# SensadoCalibradoMaquinas_v2.net
KiCad netlist of a schematic drawn in EAGLE
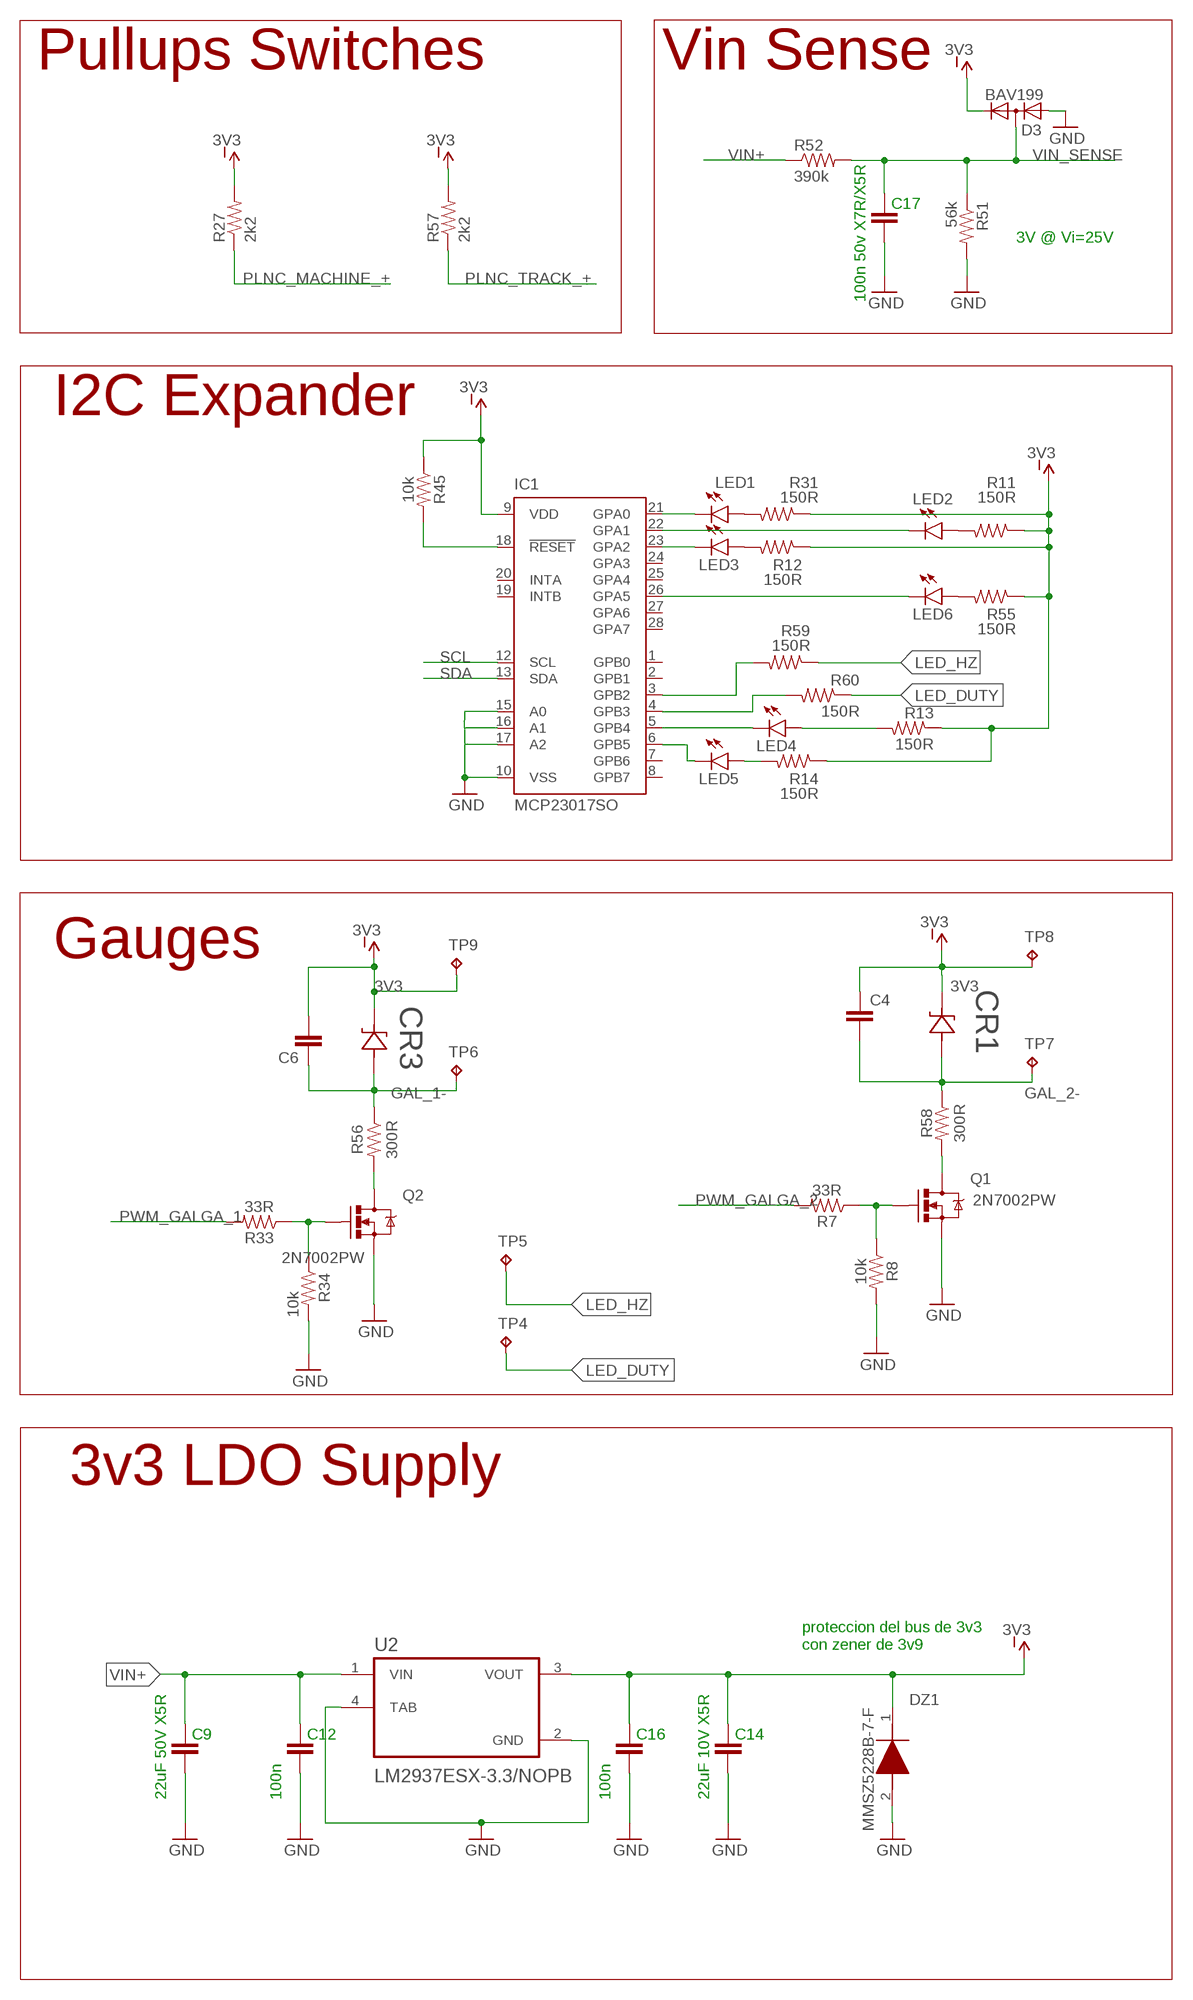
[diagram p0: schematic, sheet 1, part 1 of 2]
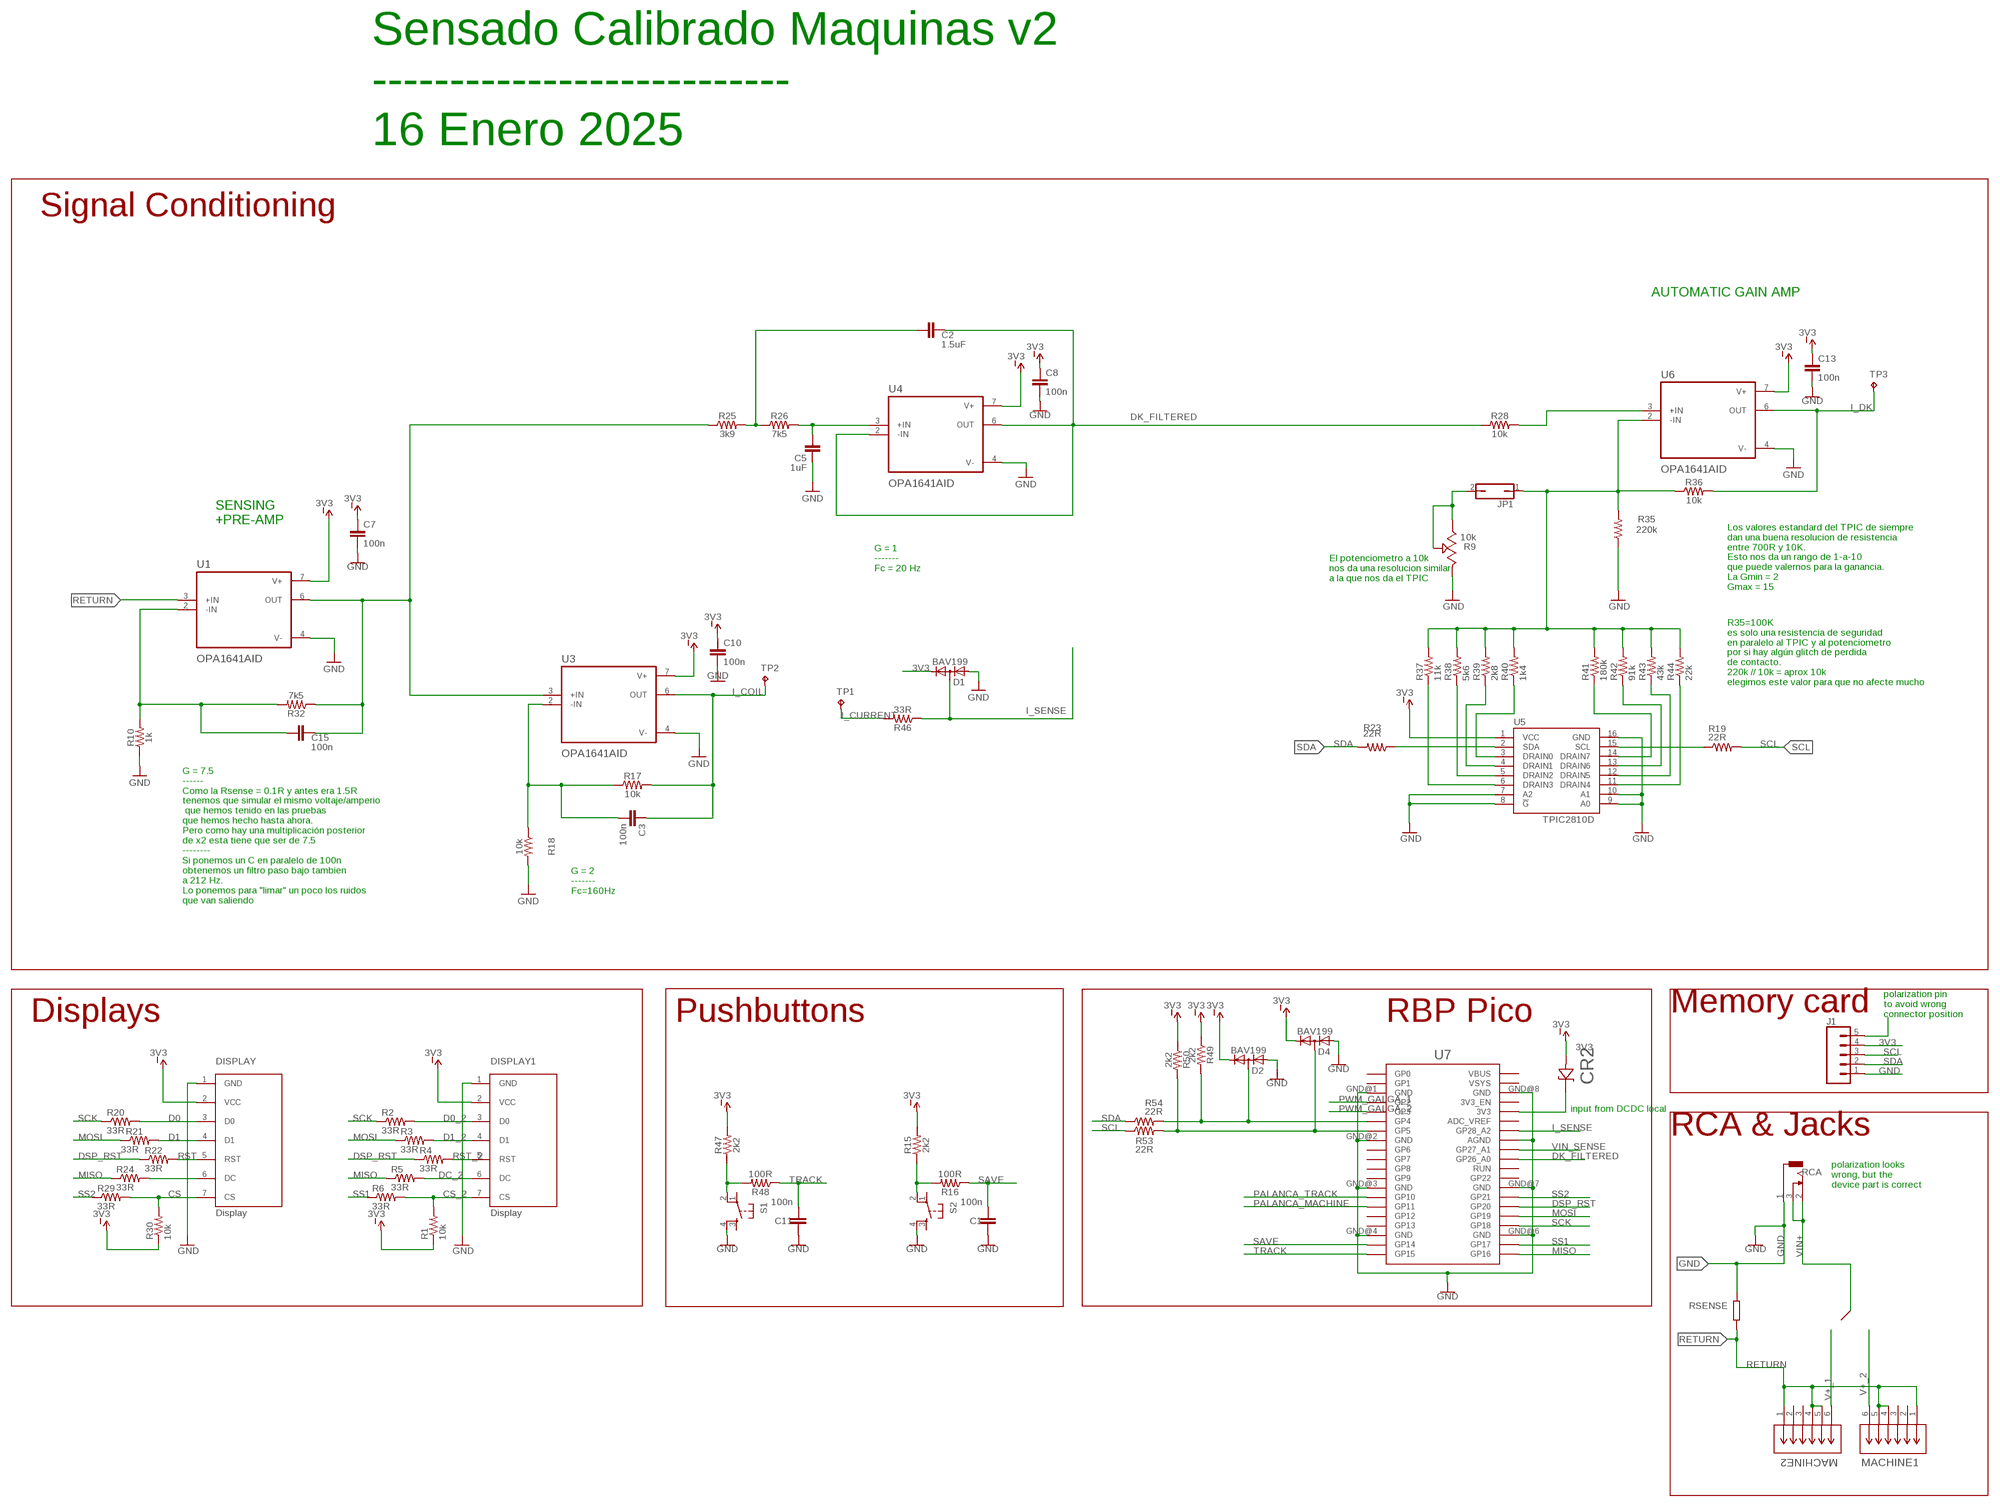
[diagram p1: schematic, sheet 1, part 2 of 2]

(export (version "E")
  (design (tool "Eeschema 10.0.6"))
  (components
    (comp (ref "C1")
      (value "100n")
      (footprint "eagle-import:0805")
      (libsource (lib "eagle-import") (part "1.0UF-0805-25V-(+80/-20%)"))
    )
    (comp (ref "C2")
      (value "1.5uF")
      (footprint "eagle-import:0805")
      (libsource (lib "eagle-import") (part "CAP0805"))
    )
    (comp (ref "C3")
      (value "100n")
      (footprint "eagle-import:0805")
      (libsource (lib "eagle-import") (part "CAP0805"))
    )
    (comp (ref "C4")
      (value "CAP0805")
      (footprint "eagle-import:0805")
      (libsource (lib "eagle-import") (part "CAP0805"))
    )
    (comp (ref "C5")
      (value "1uF")
      (footprint "eagle-import:0805")
      (libsource (lib "eagle-import") (part "CAP0805"))
    )
    (comp (ref "C6")
      (value "CAP0805")
      (footprint "eagle-import:0805")
      (libsource (lib "eagle-import") (part "CAP0805"))
    )
    (comp (ref "C7")
      (value "100n")
      (footprint "eagle-import:0805")
      (libsource (lib "eagle-import") (part "1.0UF-0805-25V-(+80/-20%)"))
    )
    (comp (ref "C8")
      (value "100n")
      (footprint "eagle-import:0805")
      (libsource (lib "eagle-import") (part "1.0UF-0805-25V-(+80/-20%)"))
    )
    (comp (ref "C9")
      (value "22uF 50V X5R")
      (footprint "eagle-import:0805")
      (libsource (lib "eagle-import") (part "CAP0805"))
    )
    (comp (ref "C10")
      (value "100n")
      (footprint "eagle-import:0805")
      (libsource (lib "eagle-import") (part "1.0UF-0805-25V-(+80/-20%)"))
    )
    (comp (ref "C11")
      (value "100n")
      (footprint "eagle-import:0805")
      (libsource (lib "eagle-import") (part "1.0UF-0805-25V-(+80/-20%)"))
    )
    (comp (ref "C12")
      (value "100n")
      (footprint "eagle-import:0805")
      (libsource (lib "eagle-import") (part "CAP0805"))
    )
    (comp (ref "C13")
      (value "100n")
      (footprint "eagle-import:0805")
      (libsource (lib "eagle-import") (part "1.0UF-0805-25V-(+80/-20%)"))
    )
    (comp (ref "C14")
      (value "22uF 10V X5R")
      (footprint "eagle-import:0805")
      (libsource (lib "eagle-import") (part "CAP0805"))
    )
    (comp (ref "C15")
      (value "100n")
      (footprint "eagle-import:0805")
      (libsource (lib "eagle-import") (part "CAP0805"))
    )
    (comp (ref "C16")
      (value "100n")
      (footprint "eagle-import:0805")
      (libsource (lib "eagle-import") (part "CAP0805"))
    )
    (comp (ref "C17")
      (value "100n 50v X7R/X5R")
      (footprint "eagle-import:0805")
      (libsource (lib "eagle-import") (part "CAP0805"))
    )
    (comp (ref "CR1")
      (value "STPS1L40U")
      (footprint "eagle-import:SMB_STM")
      (fields (field (name "COPYRIGHT") "Copyright (C) 2024 Ultra Librarian. All rights reserved."))
      (libsource (lib "eagle-import") (part "STPS1L40U"))
    )
    (comp (ref "CR2")
      (value "STPS1L40U")
      (footprint "eagle-import:SMB_STM")
      (fields (field (name "COPYRIGHT") "Copyright (C) 2024 Ultra Librarian. All rights reserved."))
      (libsource (lib "eagle-import") (part "STPS1L40U"))
    )
    (comp (ref "CR3")
      (value "STPS1L40U")
      (footprint "eagle-import:SMB_STM")
      (fields (field (name "COPYRIGHT") "Copyright (C) 2024 Ultra Librarian. All rights reserved."))
      (libsource (lib "eagle-import") (part "STPS1L40U"))
    )
    (comp (ref "D1")
      (value "BAV199")
      (footprint "eagle-import:SOT23")
      (libsource (lib "eagle-import") (part "BAV199"))
    )
    (comp (ref "D2")
      (value "BAV199")
      (footprint "eagle-import:SOT23")
      (libsource (lib "eagle-import") (part "BAV199"))
    )
    (comp (ref "D3")
      (value "BAV199")
      (footprint "eagle-import:SOT23")
      (libsource (lib "eagle-import") (part "BAV199"))
    )
    (comp (ref "D4")
      (value "BAV199")
      (footprint "eagle-import:SOT23")
      (libsource (lib "eagle-import") (part "BAV199"))
    )
    (comp (ref "DISPLAY")
      (value "Display")
      (footprint "eagle-import:OLED_LCD")
      (libsource (lib "eagle-import") (part "OLED_LCD"))
    )
    (comp (ref "DISPLAY1")
      (value "Display")
      (footprint "eagle-import:OLED_LCD")
      (libsource (lib "eagle-import") (part "OLED_LCD"))
    )
    (comp (ref "DZ1")
      (value "MMSZ5228B-7-F")
      (footprint "eagle-import:SODFL3518X115N")
      (libsource (lib "eagle-import") (part "MMSZ5228B-7-F"))
    )
    (comp (ref "IC1")
      (value "MCP23017SO")
      (footprint "eagle-import:SO28W")
      (libsource (lib "eagle-import") (part "MCP23017SO"))
    )
    (comp (ref "J1")
      (value "CONN_05")
      (footprint "eagle-import:1X05")
      (libsource (lib "eagle-import") (part "CONN_05"))
    )
    (comp (ref "JP1")
      (value "JP1Q")
      (footprint "eagle-import:JP1")
      (libsource (lib "eagle-import") (part "JP1Q"))
    )
    (comp (ref "LED1")
      (value "LED3MM")
      (footprint "eagle-import:LED3MM")
      (libsource (lib "eagle-import") (part "LED3MM"))
    )
    (comp (ref "LED2")
      (value "LED3MM")
      (footprint "eagle-import:LED3MM")
      (libsource (lib "eagle-import") (part "LED3MM"))
    )
    (comp (ref "LED3")
      (value "LED3MM")
      (footprint "eagle-import:LED3MM")
      (libsource (lib "eagle-import") (part "LED3MM"))
    )
    (comp (ref "LED4")
      (value "LED3MM")
      (footprint "eagle-import:LED3MM")
      (libsource (lib "eagle-import") (part "LED3MM"))
    )
    (comp (ref "LED5")
      (value "LED3MM")
      (footprint "eagle-import:LED3MM")
      (libsource (lib "eagle-import") (part "LED3MM"))
    )
    (comp (ref "LED6")
      (value "LED3MM")
      (footprint "eagle-import:LED3MM")
      (libsource (lib "eagle-import") (part "LED3MM"))
    )
    (comp (ref "MACHINE1")
      (value "ACJS-MHDR")
      (footprint "eagle-import:CONN_MHDR_AMP")
      (fields (field (name "COPYRIGHT") "Copyright (C) 2018 Accelerated Designs. All rights reserved"))
      (libsource (lib "eagle-import") (part "ACJS-MHDR"))
    )
    (comp (ref "MACHINE2")
      (value "ACJS-MHDR")
      (footprint "eagle-import:CONN_MHDR_AMP")
      (fields (field (name "COPYRIGHT") "Copyright (C) 2018 Accelerated Designs. All rights reserved"))
      (libsource (lib "eagle-import") (part "ACJS-MHDR"))
    )
    (comp (ref "Q1")
      (value "2N7002PW")
      (footprint "eagle-import:SOT323")
      (libsource (lib "eagle-import") (part "MOSFET-NCHANNEL2N7002PW"))
    )
    (comp (ref "Q2")
      (value "2N7002PW")
      (footprint "eagle-import:SOT323")
      (libsource (lib "eagle-import") (part "MOSFET-NCHANNEL2N7002PW"))
    )
    (comp (ref "R1")
      (value "10k")
      (footprint "eagle-import:0805")
      (libsource (lib "eagle-import") (part "RESISTOR0805"))
    )
    (comp (ref "R2")
      (value "33R")
      (footprint "eagle-import:0805")
      (libsource (lib "eagle-import") (part "RESISTOR0805"))
    )
    (comp (ref "R3")
      (value "33R")
      (footprint "eagle-import:0805")
      (libsource (lib "eagle-import") (part "RESISTOR0805"))
    )
    (comp (ref "R4")
      (value "33R")
      (footprint "eagle-import:0805")
      (libsource (lib "eagle-import") (part "RESISTOR0805"))
    )
    (comp (ref "R5")
      (value "33R")
      (footprint "eagle-import:0805")
      (libsource (lib "eagle-import") (part "RESISTOR0805"))
    )
    (comp (ref "R6")
      (value "33R")
      (footprint "eagle-import:0805")
      (libsource (lib "eagle-import") (part "RESISTOR0805"))
    )
    (comp (ref "R7")
      (value "33R")
      (footprint "eagle-import:0805")
      (libsource (lib "eagle-import") (part "RESISTOR0805"))
    )
    (comp (ref "R8")
      (value "10k")
      (footprint "eagle-import:0805")
      (libsource (lib "eagle-import") (part "RESISTOR0805"))
    )
    (comp (ref "R9")
      (value "10k")
      (footprint "eagle-import:TRIM_PT01-D120D-B104")
      (fields (field (name "MANUFACTURER") "CUI Devices"))
      (libsource (lib "eagle-import") (part "PT01-D120D-B104"))
    )
    (comp (ref "R10")
      (value "1k")
      (footprint "eagle-import:0805")
      (libsource (lib "eagle-import") (part "RESISTOR0805"))
    )
    (comp (ref "R11")
      (value "150R")
      (footprint "eagle-import:0805")
      (libsource (lib "eagle-import") (part "RESISTOR0805"))
    )
    (comp (ref "R12")
      (value "150R")
      (footprint "eagle-import:0805")
      (libsource (lib "eagle-import") (part "RESISTOR0805"))
    )
    (comp (ref "R13")
      (value "150R")
      (footprint "eagle-import:0805")
      (libsource (lib "eagle-import") (part "RESISTOR0805"))
    )
    (comp (ref "R14")
      (value "150R")
      (footprint "eagle-import:0805")
      (libsource (lib "eagle-import") (part "RESISTOR0805"))
    )
    (comp (ref "R15")
      (value "2k2")
      (footprint "eagle-import:0805")
      (libsource (lib "eagle-import") (part "RESISTOR0805"))
    )
    (comp (ref "R16")
      (value "100R")
      (footprint "eagle-import:0805")
      (libsource (lib "eagle-import") (part "RESISTOR0805"))
    )
    (comp (ref "R17")
      (value "10k")
      (footprint "eagle-import:0805")
      (libsource (lib "eagle-import") (part "RESISTOR0805"))
    )
    (comp (ref "R18")
      (value "10k")
      (footprint "eagle-import:0805")
      (libsource (lib "eagle-import") (part "RESISTOR0805"))
    )
    (comp (ref "R19")
      (value "22R")
      (footprint "eagle-import:0805")
      (libsource (lib "eagle-import") (part "RESISTOR0805"))
    )
    (comp (ref "R20")
      (value "33R")
      (footprint "eagle-import:0805")
      (libsource (lib "eagle-import") (part "RESISTOR0805"))
    )
    (comp (ref "R21")
      (value "33R")
      (footprint "eagle-import:0805")
      (libsource (lib "eagle-import") (part "RESISTOR0805"))
    )
    (comp (ref "R22")
      (value "33R")
      (footprint "eagle-import:0805")
      (libsource (lib "eagle-import") (part "RESISTOR0805"))
    )
    (comp (ref "R23")
      (value "22R")
      (footprint "eagle-import:0805")
      (libsource (lib "eagle-import") (part "RESISTOR0805"))
    )
    (comp (ref "R24")
      (value "33R")
      (footprint "eagle-import:0805")
      (libsource (lib "eagle-import") (part "RESISTOR0805"))
    )
    (comp (ref "R25")
      (value "3k9")
      (footprint "eagle-import:0805")
      (libsource (lib "eagle-import") (part "RESISTOR0805"))
    )
    (comp (ref "R26")
      (value "7k5")
      (footprint "eagle-import:0805")
      (libsource (lib "eagle-import") (part "RESISTOR0805"))
    )
    (comp (ref "R27")
      (value "2k2")
      (footprint "eagle-import:0805")
      (libsource (lib "eagle-import") (part "RESISTOR0805"))
    )
    (comp (ref "R28")
      (value "10k")
      (footprint "eagle-import:0805")
      (libsource (lib "eagle-import") (part "RESISTOR0805"))
    )
    (comp (ref "R29")
      (value "33R")
      (footprint "eagle-import:0805")
      (libsource (lib "eagle-import") (part "RESISTOR0805"))
    )
    (comp (ref "R30")
      (value "10k")
      (footprint "eagle-import:0805")
      (libsource (lib "eagle-import") (part "RESISTOR0805"))
    )
    (comp (ref "R31")
      (value "150R")
      (footprint "eagle-import:0805")
      (libsource (lib "eagle-import") (part "RESISTOR0805"))
    )
    (comp (ref "R32")
      (value "7k5")
      (footprint "eagle-import:0805")
      (libsource (lib "eagle-import") (part "RESISTOR0805"))
    )
    (comp (ref "R33")
      (value "33R")
      (footprint "eagle-import:0805")
      (libsource (lib "eagle-import") (part "RESISTOR0805"))
    )
    (comp (ref "R34")
      (value "10k")
      (footprint "eagle-import:0805")
      (libsource (lib "eagle-import") (part "RESISTOR0805"))
    )
    (comp (ref "R35")
      (value "220k")
      (footprint "eagle-import:0805")
      (libsource (lib "eagle-import") (part "RESISTOR0805"))
    )
    (comp (ref "R36")
      (value "10k")
      (footprint "eagle-import:0805")
      (libsource (lib "eagle-import") (part "RESISTOR0805"))
    )
    (comp (ref "R37")
      (value "11k")
      (footprint "eagle-import:0805")
      (libsource (lib "eagle-import") (part "RESISTOR0805"))
    )
    (comp (ref "R38")
      (value "5k6")
      (footprint "eagle-import:0805")
      (libsource (lib "eagle-import") (part "RESISTOR0805"))
    )
    (comp (ref "R39")
      (value "2k8")
      (footprint "eagle-import:0805")
      (libsource (lib "eagle-import") (part "RESISTOR0805"))
    )
    (comp (ref "R40")
      (value "1k4")
      (footprint "eagle-import:0805")
      (libsource (lib "eagle-import") (part "RESISTOR0805"))
    )
    (comp (ref "R41")
      (value "180k")
      (footprint "eagle-import:0805")
      (libsource (lib "eagle-import") (part "RESISTOR0805"))
    )
    (comp (ref "R42")
      (value "91k")
      (footprint "eagle-import:0805")
      (libsource (lib "eagle-import") (part "RESISTOR0805"))
    )
    (comp (ref "R43")
      (value "43k")
      (footprint "eagle-import:0805")
      (libsource (lib "eagle-import") (part "RESISTOR0805"))
    )
    (comp (ref "R44")
      (value "22k")
      (footprint "eagle-import:0805")
      (libsource (lib "eagle-import") (part "RESISTOR0805"))
    )
    (comp (ref "R45")
      (value "10k")
      (footprint "eagle-import:0805")
      (libsource (lib "eagle-import") (part "RESISTOR0805"))
    )
    (comp (ref "R46")
      (value "33R")
      (footprint "eagle-import:0805")
      (libsource (lib "eagle-import") (part "RESISTOR0805"))
    )
    (comp (ref "R47")
      (value "2k2")
      (footprint "eagle-import:0805")
      (libsource (lib "eagle-import") (part "RESISTOR0805"))
    )
    (comp (ref "R48")
      (value "100R")
      (footprint "eagle-import:0805")
      (libsource (lib "eagle-import") (part "RESISTOR0805"))
    )
    (comp (ref "R49")
      (value "2k2")
      (footprint "eagle-import:0805")
      (libsource (lib "eagle-import") (part "RESISTOR0805"))
    )
    (comp (ref "R50")
      (value "2k2")
      (footprint "eagle-import:0805")
      (libsource (lib "eagle-import") (part "RESISTOR0805"))
    )
    (comp (ref "R51")
      (value "56k")
      (footprint "eagle-import:0805")
      (libsource (lib "eagle-import") (part "RESISTOR0805"))
    )
    (comp (ref "R52")
      (value "390k")
      (footprint "eagle-import:0805")
      (libsource (lib "eagle-import") (part "RESISTOR0805"))
    )
    (comp (ref "R53")
      (value "22R")
      (footprint "eagle-import:0805")
      (libsource (lib "eagle-import") (part "RESISTOR0805"))
    )
    (comp (ref "R54")
      (value "22R")
      (footprint "eagle-import:0805")
      (libsource (lib "eagle-import") (part "RESISTOR0805"))
    )
    (comp (ref "R55")
      (value "150R")
      (footprint "eagle-import:0805")
      (libsource (lib "eagle-import") (part "RESISTOR0805"))
    )
    (comp (ref "R56")
      (value "300R")
      (footprint "eagle-import:0805")
      (libsource (lib "eagle-import") (part "RESISTOR0805"))
    )
    (comp (ref "R57")
      (value "2k2")
      (footprint "eagle-import:0805")
      (libsource (lib "eagle-import") (part "RESISTOR0805"))
    )
    (comp (ref "R58")
      (value "300R")
      (footprint "eagle-import:0805")
      (libsource (lib "eagle-import") (part "RESISTOR0805"))
    )
    (comp (ref "R59")
      (value "150R")
      (footprint "eagle-import:0805")
      (libsource (lib "eagle-import") (part "RESISTOR0805"))
    )
    (comp (ref "R60")
      (value "150R")
      (footprint "eagle-import:0805")
      (libsource (lib "eagle-import") (part "RESISTOR0805"))
    )
    (comp (ref "RCA")
      (value "PJRAN1X1U01X")
      (footprint "eagle-import:PJRAN1X1U01X")
      (fields
        (field (name "DIGIKEY_PART_NUMBER") "PJRAN1X1U01X-ND")
        (field (name "MANUFACTURER") "Switchcraft Inc.")
        (field (name "CREATED_BY") "PCBLayout.com")
      )
      (libsource (lib "eagle-import") (part "PJRAN1X1U01X"))
    )
    (comp (ref "RSENSE")
      (value "0.1R")
      (footprint "eagle-import:RESC6332X71")
      (libsource (lib "eagle-import") (part "RCHIP-2512(6332-METRIC)_"))
    )
    (comp (ref "S1")
      (value "TAC_SWITCH_KSC931G-SMD")
      (footprint "eagle-import:TAC_SW_SMD_KSC931G")
      (libsource (lib "eagle-import") (part "TAC_SWITCH_KSC931G-SMD"))
    )
    (comp (ref "S2")
      (value "TAC_SWITCH_KSC931G-SMD")
      (footprint "eagle-import:TAC_SW_SMD_KSC931G")
      (libsource (lib "eagle-import") (part "TAC_SWITCH_KSC931G-SMD"))
    )
    (comp (ref "TP1")
      (value "TPTP06SQ")
      (footprint "eagle-import:TP06SQ")
      (libsource (lib "eagle-import") (part "TPTP06SQ"))
    )
    (comp (ref "TP2")
      (value "TPTP06SQ")
      (footprint "eagle-import:TP06SQ")
      (libsource (lib "eagle-import") (part "TPTP06SQ"))
    )
    (comp (ref "TP3")
      (value "TPTP06SQ")
      (footprint "eagle-import:TP06SQ")
      (libsource (lib "eagle-import") (part "TPTP06SQ"))
    )
    (comp (ref "TP4")
      (value "TPTP06SQ")
      (footprint "eagle-import:TP06SQ")
      (libsource (lib "eagle-import") (part "TPTP06SQ"))
    )
    (comp (ref "TP5")
      (value "TPTP06SQ")
      (footprint "eagle-import:TP06SQ")
      (libsource (lib "eagle-import") (part "TPTP06SQ"))
    )
    (comp (ref "TP6")
      (value "TPTP06SQ")
      (footprint "eagle-import:TP06SQ")
      (libsource (lib "eagle-import") (part "TPTP06SQ"))
    )
    (comp (ref "TP7")
      (value "TPTP06SQ")
      (footprint "eagle-import:TP06SQ")
      (libsource (lib "eagle-import") (part "TPTP06SQ"))
    )
    (comp (ref "TP8")
      (value "TPTP06SQ")
      (footprint "eagle-import:TP06SQ")
      (libsource (lib "eagle-import") (part "TPTP06SQ"))
    )
    (comp (ref "TP9")
      (value "TPTP06SQ")
      (footprint "eagle-import:TP06SQ")
      (libsource (lib "eagle-import") (part "TPTP06SQ"))
    )
    (comp (ref "U1")
      (value "OPA1641AID")
      (footprint "eagle-import:SOIC127P599X175-8N")
      (libsource (lib "eagle-import") (part "OPA1641AID"))
    )
    (comp (ref "U2")
      (value "LM2937ESX-3.3/NOPB")
      (footprint "eagle-import:TO254P1524X483-4N")
      (libsource (lib "eagle-import") (part "LM2937ESX-3.3/NOPB"))
    )
    (comp (ref "U3")
      (value "OPA1641AID")
      (footprint "eagle-import:SOIC127P599X175-8N")
      (libsource (lib "eagle-import") (part "OPA1641AID"))
    )
    (comp (ref "U4")
      (value "OPA1641AID")
      (footprint "eagle-import:SOIC127P599X175-8N")
      (libsource (lib "eagle-import") (part "OPA1641AID"))
    )
    (comp (ref "U5")
      (value "TPIC2810D")
      (footprint "eagle-import:SO16")
      (libsource (lib "eagle-import") (part "TPIC2810D"))
    )
    (comp (ref "U6")
      (value "OPA1641AID")
      (footprint "eagle-import:SOIC127P599X175-8N")
      (libsource (lib "eagle-import") (part "OPA1641AID"))
    )
    (comp (ref "U7")
      (value "RPI_PICO_IG-TH")
      (footprint "eagle-import:RPI_PICO_TH")
      (libsource (lib "eagle-import") (part "RPI_PICO_IG-TH"))
    )
  )
  (nets
    (net (code "1") (name "/CS") (class "Default")
      (node (ref "DISPLAY") (pin "7") (pinfunction "CS_7") (pintype "bidirectional"))
      (node (ref "R29") (pin "2") (pinfunction "2_2") (pintype "passive"))
      (node (ref "R30") (pin "2") (pinfunction "2_2") (pintype "passive"))
    )
    (net (code "2") (name "/CS_2") (class "Default")
      (node (ref "DISPLAY1") (pin "7") (pinfunction "CS_7") (pintype "bidirectional"))
      (node (ref "R1") (pin "2") (pinfunction "2_2") (pintype "passive"))
      (node (ref "R6") (pin "2") (pinfunction "2_2") (pintype "passive"))
    )
    (net (code "3") (name "/D0") (class "Default")
      (node (ref "DISPLAY") (pin "3") (pinfunction "D0_3") (pintype "bidirectional"))
      (node (ref "R20") (pin "2") (pinfunction "2_2") (pintype "passive"))
    )
    (net (code "4") (name "/D0_2") (class "Default")
      (node (ref "DISPLAY1") (pin "3") (pinfunction "D0_3") (pintype "bidirectional"))
      (node (ref "R2") (pin "2") (pinfunction "2_2") (pintype "passive"))
    )
    (net (code "5") (name "/D1") (class "Default")
      (node (ref "DISPLAY") (pin "4") (pinfunction "D1_4") (pintype "bidirectional"))
      (node (ref "R21") (pin "2") (pinfunction "2_2") (pintype "passive"))
    )
    (net (code "6") (name "/D1_2") (class "Default")
      (node (ref "DISPLAY1") (pin "4") (pinfunction "D1_4") (pintype "bidirectional"))
      (node (ref "R3") (pin "2") (pinfunction "2_2") (pintype "passive"))
    )
    (net (code "7") (name "/DC_2") (class "Default")
      (node (ref "DISPLAY1") (pin "6") (pinfunction "DC_6") (pintype "bidirectional"))
      (node (ref "R5") (pin "2") (pinfunction "2_2") (pintype "passive"))
    )
    (net (code "8") (name "/DK_FILTERED") (class "Default")
      (node (ref "C2") (pin "1") (pinfunction "1_1") (pintype "passive"))
      (node (ref "R28") (pin "1") (pinfunction "1_1") (pintype "passive"))
      (node (ref "U4") (pin "2") (pinfunction "-IN_2") (pintype "input"))
      (node (ref "U4") (pin "6") (pinfunction "OUT_6") (pintype "output"))
      (node (ref "U7") (pin "GP26_A0") (pinfunction "GP26_A0_GP26_A0") (pintype "bidirectional"))
    )
    (net (code "9") (name "/DSP_RST") (class "Default")
      (node (ref "R22") (pin "1") (pinfunction "1_1") (pintype "passive"))
      (node (ref "R4") (pin "1") (pinfunction "1_1") (pintype "passive"))
      (node (ref "U7") (pin "GP20") (pinfunction "GP20_GP20") (pintype "bidirectional"))
    )
    (net (code "10") (name "/GAL_1-") (class "Default")
      (node (ref "C6") (pin "1") (pinfunction "1_1") (pintype "passive"))
      (node (ref "CR3") (pin "1") (pinfunction "1_1") (pintype "passive"))
      (node (ref "R56") (pin "1") (pinfunction "1_1") (pintype "passive"))
      (node (ref "TP6") (pin "TP") (pinfunction "TP_TP") (pintype "input"))
    )
    (net (code "11") (name "/GAL_2-") (class "Default")
      (node (ref "C4") (pin "2") (pinfunction "2_2") (pintype "passive"))
      (node (ref "CR1") (pin "1") (pinfunction "1_1") (pintype "passive"))
      (node (ref "R58") (pin "1") (pinfunction "1_1") (pintype "passive"))
      (node (ref "TP7") (pin "TP") (pinfunction "TP_TP") (pintype "input"))
    )
    (net (code "12") (name "/I_COIL") (class "Default")
      (node (ref "C3") (pin "1") (pinfunction "1_1") (pintype "passive"))
      (node (ref "R17") (pin "2") (pinfunction "2_2") (pintype "passive"))
      (node (ref "TP2") (pin "TP") (pinfunction "TP_TP") (pintype "input"))
      (node (ref "U3") (pin "6") (pinfunction "OUT_6") (pintype "output"))
    )
    (net (code "13") (name "/I_CURRENT") (class "Default")
      (node (ref "R46") (pin "2") (pinfunction "2_2") (pintype "passive"))
      (node (ref "TP1") (pin "TP") (pinfunction "TP_TP") (pintype "input"))
    )
    (net (code "14") (name "/I_DK") (class "Default")
      (node (ref "R36") (pin "2") (pinfunction "2_2") (pintype "passive"))
      (node (ref "TP3") (pin "TP") (pinfunction "TP_TP") (pintype "input"))
      (node (ref "U6") (pin "6") (pinfunction "OUT_6") (pintype "output"))
    )
    (net (code "15") (name "/I_SENSE") (class "Default")
      (node (ref "D1") (pin "3") (pinfunction "AC_3") (pintype "passive"))
      (node (ref "R46") (pin "1") (pinfunction "1_1") (pintype "passive"))
      (node (ref "U7") (pin "GP28_A2") (pinfunction "GP28_A2_GP28_A2") (pintype "bidirectional"))
    )
    (net (code "16") (name "/MISO") (class "Default")
      (node (ref "R24") (pin "1") (pinfunction "1_1") (pintype "passive"))
      (node (ref "R5") (pin "1") (pinfunction "1_1") (pintype "passive"))
      (node (ref "U7") (pin "GP16") (pinfunction "GP16_GP16") (pintype "bidirectional"))
    )
    (net (code "17") (name "/MOSI") (class "Default")
      (node (ref "R21") (pin "1") (pinfunction "1_1") (pintype "passive"))
      (node (ref "R3") (pin "1") (pinfunction "1_1") (pintype "passive"))
      (node (ref "U7") (pin "GP19") (pinfunction "GP19_GP19") (pintype "bidirectional"))
    )
    (net (code "18") (name "/PALANCA_MACHINE") (class "Default")
      (node (ref "U7") (pin "GP11") (pinfunction "GP11_GP11") (pintype "bidirectional"))
    )
    (net (code "19") (name "/PALANCA_TRACK") (class "Default")
      (node (ref "U7") (pin "GP10") (pinfunction "GP10_GP10") (pintype "bidirectional"))
    )
    (net (code "20") (name "/PLNC_MACHINE_+") (class "Default")
      (node (ref "R27") (pin "1") (pinfunction "1_1") (pintype "passive"))
    )
    (net (code "21") (name "/PLNC_TRACK_+") (class "Default")
      (node (ref "R57") (pin "1") (pinfunction "1_1") (pintype "passive"))
    )
    (net (code "22") (name "/PWM_GALGA_1") (class "Default")
      (node (ref "R33") (pin "2") (pinfunction "2_2") (pintype "passive"))
      (node (ref "U7") (pin "GP2") (pinfunction "GP2_GP2") (pintype "bidirectional"))
    )
    (net (code "23") (name "/PWM_GALGA_2") (class "Default")
      (node (ref "R7") (pin "2") (pinfunction "2_2") (pintype "passive"))
      (node (ref "U7") (pin "GP3") (pinfunction "GP3_GP3") (pintype "bidirectional"))
    )
    (net (code "24") (name "/RST") (class "Default")
      (node (ref "DISPLAY") (pin "5") (pinfunction "RST_5") (pintype "bidirectional"))
      (node (ref "R22") (pin "2") (pinfunction "2_2") (pintype "passive"))
    )
    (net (code "25") (name "/RST_2") (class "Default")
      (node (ref "DISPLAY1") (pin "5") (pinfunction "RST_5") (pintype "bidirectional"))
      (node (ref "R4") (pin "2") (pinfunction "2_2") (pintype "passive"))
    )
    (net (code "26") (name "/SAVE") (class "Default")
      (node (ref "C1") (pin "2") (pinfunction "2_2") (pintype "passive"))
      (node (ref "R16") (pin "1") (pinfunction "1_1") (pintype "passive"))
      (node (ref "U7") (pin "GP14") (pinfunction "GP14_GP14") (pintype "bidirectional"))
    )
    (net (code "27") (name "/SCK") (class "Default")
      (node (ref "R2") (pin "1") (pinfunction "1_1") (pintype "passive"))
      (node (ref "R20") (pin "1") (pinfunction "1_1") (pintype "passive"))
      (node (ref "U7") (pin "GP18") (pinfunction "GP18_GP18") (pintype "bidirectional"))
    )
    (net (code "28") (name "/SS1") (class "Default")
      (node (ref "R6") (pin "1") (pinfunction "1_1") (pintype "passive"))
      (node (ref "U7") (pin "GP17") (pinfunction "GP17_GP17") (pintype "bidirectional"))
    )
    (net (code "29") (name "/SS2") (class "Default")
      (node (ref "R29") (pin "1") (pinfunction "1_1") (pintype "passive"))
      (node (ref "U7") (pin "GP21") (pinfunction "GP21_GP21") (pintype "bidirectional"))
    )
    (net (code "30") (name "/TRACK") (class "Default")
      (node (ref "C11") (pin "2") (pinfunction "2_2") (pintype "passive"))
      (node (ref "R48") (pin "1") (pinfunction "1_1") (pintype "passive"))
      (node (ref "U7") (pin "GP15") (pinfunction "GP15_GP15") (pintype "bidirectional"))
    )
    (net (code "31") (name "/V+_1") (class "Default")
      (node (ref "MACHINE2") (pin "6") (pinfunction "6_6") (pintype "passive"))
    )
    (net (code "32") (name "/V+_2") (class "Default")
      (node (ref "MACHINE1") (pin "6") (pinfunction "6_6") (pintype "passive"))
    )
    (net (code "33") (name "/VIN_SENSE") (class "Default")
      (node (ref "C17") (pin "2") (pinfunction "2_2") (pintype "passive"))
      (node (ref "D3") (pin "3") (pinfunction "AC_3") (pintype "passive"))
      (node (ref "R51") (pin "1") (pinfunction "1_1") (pintype "passive"))
      (node (ref "R52") (pin "2") (pinfunction "2_2") (pintype "passive"))
      (node (ref "U7") (pin "GP27_A1") (pinfunction "GP27_A1_GP27_A1") (pintype "bidirectional"))
    )
    (net (code "34") (name "3V3") (class "Default")
      (node (ref "C10") (pin "2") (pinfunction "2_2") (pintype "passive"))
      (node (ref "C13") (pin "2") (pinfunction "2_2") (pintype "passive"))
      (node (ref "C14") (pin "2") (pinfunction "2_2") (pintype "passive"))
      (node (ref "C16") (pin "2") (pinfunction "2_2") (pintype "passive"))
      (node (ref "C4") (pin "1") (pinfunction "1_1") (pintype "passive"))
      (node (ref "C6") (pin "2") (pinfunction "2_2") (pintype "passive"))
      (node (ref "C7") (pin "2") (pinfunction "2_2") (pintype "passive"))
      (node (ref "C8") (pin "2") (pinfunction "2_2") (pintype "passive"))
      (node (ref "CR1") (pin "2") (pinfunction "2_2") (pintype "passive"))
      (node (ref "CR2") (pin "1") (pinfunction "1_1") (pintype "passive"))
      (node (ref "CR3") (pin "2") (pinfunction "2_2") (pintype "passive"))
      (node (ref "D1") (pin "2") (pinfunction "C_2") (pintype "passive"))
      (node (ref "D2") (pin "2") (pinfunction "C_2") (pintype "passive"))
      (node (ref "D3") (pin "2") (pinfunction "C_2") (pintype "passive"))
      (node (ref "D4") (pin "2") (pinfunction "C_2") (pintype "passive"))
      (node (ref "DISPLAY") (pin "2") (pinfunction "VCC_2") (pintype "bidirectional"))
      (node (ref "DISPLAY1") (pin "2") (pinfunction "VCC_2") (pintype "bidirectional"))
      (node (ref "DZ1") (pin "1") (pinfunction "K_1") (pintype "bidirectional"))
      (node (ref "IC1") (pin "9") (pinfunction "VDD_9") (pintype "power_in"))
      (node (ref "J1") (pin "4") (pinfunction "4_4") (pintype "passive"))
      (node (ref "R1") (pin "1") (pinfunction "1_1") (pintype "passive"))
      (node (ref "R11") (pin "1") (pinfunction "1_1") (pintype "passive"))
      (node (ref "R12") (pin "1") (pinfunction "1_1") (pintype "passive"))
      (node (ref "R13") (pin "1") (pinfunction "1_1") (pintype "passive"))
      (node (ref "R14") (pin "1") (pinfunction "1_1") (pintype "passive"))
      (node (ref "R15") (pin "2") (pinfunction "2_2") (pintype "passive"))
      (node (ref "R27") (pin "2") (pinfunction "2_2") (pintype "passive"))
      (node (ref "R30") (pin "1") (pinfunction "1_1") (pintype "passive"))
      (node (ref "R31") (pin "1") (pinfunction "1_1") (pintype "passive"))
      (node (ref "R45") (pin "1") (pinfunction "1_1") (pintype "passive"))
      (node (ref "R47") (pin "2") (pinfunction "2_2") (pintype "passive"))
      (node (ref "R49") (pin "1") (pinfunction "1_1") (pintype "passive"))
      (node (ref "R50") (pin "1") (pinfunction "1_1") (pintype "passive"))
      (node (ref "R55") (pin "1") (pinfunction "1_1") (pintype "passive"))
      (node (ref "R57") (pin "2") (pinfunction "2_2") (pintype "passive"))
      (node (ref "TP8") (pin "TP") (pinfunction "TP_TP") (pintype "input"))
      (node (ref "TP9") (pin "TP") (pinfunction "TP_TP") (pintype "input"))
      (node (ref "U1") (pin "7") (pinfunction "V+_7") (pintype "power_in"))
      (node (ref "U2") (pin "3") (pinfunction "VOUT_3") (pintype "output"))
      (node (ref "U3") (pin "7") (pinfunction "V+_7") (pintype "power_in"))
      (node (ref "U4") (pin "7") (pinfunction "V+_7") (pintype "power_in"))
      (node (ref "U5") (pin "1") (pinfunction "VCC_1") (pintype "bidirectional"))
      (node (ref "U6") (pin "7") (pinfunction "V+_7") (pintype "power_in"))
    )
    (net (code "35") (name "GND") (class "Default")
      (node (ref "C1") (pin "1") (pinfunction "1_1") (pintype "passive"))
      (node (ref "C10") (pin "1") (pinfunction "1_1") (pintype "passive"))
      (node (ref "C11") (pin "1") (pinfunction "1_1") (pintype "passive"))
      (node (ref "C12") (pin "1") (pinfunction "1_1") (pintype "passive"))
      (node (ref "C13") (pin "1") (pinfunction "1_1") (pintype "passive"))
      (node (ref "C14") (pin "1") (pinfunction "1_1") (pintype "passive"))
      (node (ref "C16") (pin "1") (pinfunction "1_1") (pintype "passive"))
      (node (ref "C17") (pin "1") (pinfunction "1_1") (pintype "passive"))
      (node (ref "C5") (pin "1") (pinfunction "1_1") (pintype "passive"))
      (node (ref "C7") (pin "1") (pinfunction "1_1") (pintype "passive"))
      (node (ref "C8") (pin "1") (pinfunction "1_1") (pintype "passive"))
      (node (ref "C9") (pin "1") (pinfunction "1_1") (pintype "passive"))
      (node (ref "D1") (pin "1") (pinfunction "A_1") (pintype "passive"))
      (node (ref "D2") (pin "1") (pinfunction "A_1") (pintype "passive"))
      (node (ref "D3") (pin "1") (pinfunction "A_1") (pintype "passive"))
      (node (ref "D4") (pin "1") (pinfunction "A_1") (pintype "passive"))
      (node (ref "DISPLAY") (pin "1") (pinfunction "GND_1") (pintype "bidirectional"))
      (node (ref "DISPLAY1") (pin "1") (pinfunction "GND_1") (pintype "bidirectional"))
      (node (ref "DZ1") (pin "2") (pinfunction "A_2") (pintype "bidirectional"))
      (node (ref "IC1") (pin "10") (pinfunction "VSS_10") (pintype "power_in"))
      (node (ref "IC1") (pin "15") (pinfunction "A0_15") (pintype "input"))
      (node (ref "IC1") (pin "16") (pinfunction "A1_16") (pintype "input"))
      (node (ref "IC1") (pin "17") (pinfunction "A2_17") (pintype "input"))
      (node (ref "J1") (pin "1") (pinfunction "1_1") (pintype "passive"))
      (node (ref "Q1") (pin "2") (pinfunction "S_2") (pintype "passive"))
      (node (ref "Q2") (pin "2") (pinfunction "S_2") (pintype "passive"))
      (node (ref "R10") (pin "1") (pinfunction "1_1") (pintype "passive"))
      (node (ref "R18") (pin "2") (pinfunction "2_2") (pintype "passive"))
      (node (ref "R34") (pin "2") (pinfunction "2_2") (pintype "passive"))
      (node (ref "R35") (pin "1") (pinfunction "1_1") (pintype "passive"))
      (node (ref "R51") (pin "2") (pinfunction "2_2") (pintype "passive"))
      (node (ref "R8") (pin "2") (pinfunction "2_2") (pintype "passive"))
      (node (ref "R9") (pin "1") (pinfunction "1_1") (pintype "passive"))
      (node (ref "RCA") (pin "1") (pinfunction "1_1") (pintype "passive"))
      (node (ref "RSENSE") (pin "2") (pinfunction "2_2") (pintype "passive"))
      (node (ref "S1") (pin "4") (pinfunction "4_4") (pintype "passive"))
      (node (ref "S2") (pin "4") (pinfunction "4_4") (pintype "passive"))
      (node (ref "U1") (pin "4") (pinfunction "V-_4") (pintype "power_in"))
      (node (ref "U2") (pin "2") (pinfunction "GND_2") (pintype "power_in"))
      (node (ref "U2") (pin "4") (pinfunction "TAB_4") (pintype "bidirectional"))
      (node (ref "U3") (pin "4") (pinfunction "V-_4") (pintype "power_in"))
      (node (ref "U4") (pin "4") (pinfunction "V-_4") (pintype "power_in"))
      (node (ref "U5") (pin "10") (pinfunction "A1_10") (pintype "bidirectional"))
      (node (ref "U5") (pin "16") (pinfunction "GND_16") (pintype "bidirectional"))
      (node (ref "U5") (pin "7") (pinfunction "A2_7") (pintype "bidirectional"))
      (node (ref "U5") (pin "8") (pinfunction "~{G}_8") (pintype "bidirectional"))
      (node (ref "U5") (pin "9") (pinfunction "A0_9") (pintype "bidirectional"))
      (node (ref "U6") (pin "4") (pinfunction "V-_4") (pintype "power_in"))
      (node (ref "U7") (pin "AGND") (pinfunction "AGND_AGND") (pintype "bidirectional"))
      (node (ref "U7") (pin "GND@1") (pinfunction "GND_GND@1") (pintype "bidirectional"))
      (node (ref "U7") (pin "GND@2") (pinfunction "GND_GND@2") (pintype "bidirectional"))
      (node (ref "U7") (pin "GND@3") (pinfunction "GND_GND@3") (pintype "bidirectional"))
      (node (ref "U7") (pin "GND@4") (pinfunction "GND_GND@4") (pintype "bidirectional"))
      (node (ref "U7") (pin "GND@6") (pinfunction "GND_GND@6") (pintype "bidirectional"))
      (node (ref "U7") (pin "GND@7") (pinfunction "GND_GND@7") (pintype "bidirectional"))
      (node (ref "U7") (pin "GND@8") (pinfunction "GND_GND@8") (pintype "bidirectional"))
    )
    (net (code "36") (name "LED_DUTY") (class "Default")
      (node (ref "R60") (pin "1") (pinfunction "1_1") (pintype "passive"))
      (node (ref "TP4") (pin "TP") (pinfunction "TP_TP") (pintype "input"))
    )
    (net (code "37") (name "LED_HZ") (class "Default")
      (node (ref "R59") (pin "1") (pinfunction "1_1") (pintype "passive"))
      (node (ref "TP5") (pin "TP") (pinfunction "TP_TP") (pintype "input"))
    )
    (net (code "38") (name "Net-(C2-Pad2)") (class "Default")
      (node (ref "C2") (pin "2") (pinfunction "2_2") (pintype "passive"))
      (node (ref "R25") (pin "2") (pinfunction "2_2") (pintype "passive"))
      (node (ref "R26") (pin "1") (pinfunction "1_1") (pintype "passive"))
    )
    (net (code "39") (name "Net-(CR2-Pad2)") (class "Default")
      (node (ref "CR2") (pin "2") (pinfunction "2_2") (pintype "passive"))
      (node (ref "U7") (pin "3V3") (pinfunction "3V3_3V3") (pintype "bidirectional"))
    )
    (net (code "40") (name "Net-(D2-AC)") (class "Default")
      (node (ref "D2") (pin "3") (pinfunction "AC_3") (pintype "passive"))
      (node (ref "R49") (pin "2") (pinfunction "2_2") (pintype "passive"))
      (node (ref "R54") (pin "2") (pinfunction "2_2") (pintype "passive"))
      (node (ref "U7") (pin "GP4") (pinfunction "GP4_GP4") (pintype "bidirectional"))
    )
    (net (code "41") (name "Net-(D4-AC)") (class "Default")
      (node (ref "D4") (pin "3") (pinfunction "AC_3") (pintype "passive"))
      (node (ref "R50") (pin "2") (pinfunction "2_2") (pintype "passive"))
      (node (ref "R53") (pin "2") (pinfunction "2_2") (pintype "passive"))
      (node (ref "U7") (pin "GP5") (pinfunction "GP5_GP5") (pintype "bidirectional"))
    )
    (net (code "42") (name "Net-(DISPLAY-DC)") (class "Default")
      (node (ref "DISPLAY") (pin "6") (pinfunction "DC_6") (pintype "bidirectional"))
      (node (ref "R24") (pin "2") (pinfunction "2_2") (pintype "passive"))
    )
    (net (code "43") (name "Net-(IC1-GPA0)") (class "Default")
      (node (ref "IC1") (pin "21") (pinfunction "GPA0_21") (pintype "bidirectional"))
      (node (ref "LED1") (pin "K") (pinfunction "C_K") (pintype "passive"))
    )
    (net (code "44") (name "Net-(IC1-GPA1)") (class "Default")
      (node (ref "IC1") (pin "22") (pinfunction "GPA1_22") (pintype "bidirectional"))
      (node (ref "LED2") (pin "K") (pinfunction "C_K") (pintype "passive"))
    )
    (net (code "45") (name "Net-(IC1-GPA2)") (class "Default")
      (node (ref "IC1") (pin "23") (pinfunction "GPA2_23") (pintype "bidirectional"))
      (node (ref "LED3") (pin "K") (pinfunction "C_K") (pintype "passive"))
    )
    (net (code "46") (name "Net-(IC1-GPA5)") (class "Default")
      (node (ref "IC1") (pin "26") (pinfunction "GPA5_26") (pintype "bidirectional"))
      (node (ref "LED6") (pin "K") (pinfunction "C_K") (pintype "passive"))
    )
    (net (code "47") (name "Net-(IC1-GPB2)") (class "Default")
      (node (ref "IC1") (pin "3") (pinfunction "GPB2_3") (pintype "bidirectional"))
      (node (ref "R59") (pin "2") (pinfunction "2_2") (pintype "passive"))
    )
    (net (code "48") (name "Net-(IC1-GPB3)") (class "Default")
      (node (ref "IC1") (pin "4") (pinfunction "GPB3_4") (pintype "bidirectional"))
      (node (ref "R60") (pin "2") (pinfunction "2_2") (pintype "passive"))
    )
    (net (code "49") (name "Net-(IC1-GPB4)") (class "Default")
      (node (ref "IC1") (pin "5") (pinfunction "GPB4_5") (pintype "bidirectional"))
      (node (ref "LED4") (pin "K") (pinfunction "C_K") (pintype "passive"))
    )
    (net (code "50") (name "Net-(IC1-GPB5)") (class "Default")
      (node (ref "IC1") (pin "6") (pinfunction "GPB5_6") (pintype "bidirectional"))
      (node (ref "LED5") (pin "K") (pinfunction "C_K") (pintype "passive"))
    )
    (net (code "51") (name "Net-(IC1-~{RESET})") (class "Default")
      (node (ref "IC1") (pin "18") (pinfunction "~{RESET}_18") (pintype "input"))
      (node (ref "R45") (pin "2") (pinfunction "2_2") (pintype "passive"))
    )
    (net (code "52") (name "Net-(JP1-Pad2)") (class "Default")
      (node (ref "JP1") (pin "2") (pinfunction "2_2") (pintype "passive"))
      (node (ref "R9") (pin "2") (pinfunction "2_2") (pintype "passive"))
      (node (ref "R9") (pin "3") (pinfunction "3_3") (pintype "passive"))
    )
    (net (code "53") (name "Net-(LED1-PadA)") (class "Default")
      (node (ref "LED1") (pin "A") (pinfunction "A_A") (pintype "passive"))
      (node (ref "R31") (pin "2") (pinfunction "2_2") (pintype "passive"))
    )
    (net (code "54") (name "Net-(LED2-PadA)") (class "Default")
      (node (ref "LED2") (pin "A") (pinfunction "A_A") (pintype "passive"))
      (node (ref "R11") (pin "2") (pinfunction "2_2") (pintype "passive"))
    )
    (net (code "55") (name "Net-(LED3-PadA)") (class "Default")
      (node (ref "LED3") (pin "A") (pinfunction "A_A") (pintype "passive"))
      (node (ref "R12") (pin "2") (pinfunction "2_2") (pintype "passive"))
    )
    (net (code "56") (name "Net-(LED4-PadA)") (class "Default")
      (node (ref "LED4") (pin "A") (pinfunction "A_A") (pintype "passive"))
      (node (ref "R13") (pin "2") (pinfunction "2_2") (pintype "passive"))
    )
    (net (code "57") (name "Net-(LED5-PadA)") (class "Default")
      (node (ref "LED5") (pin "A") (pinfunction "A_A") (pintype "passive"))
      (node (ref "R14") (pin "2") (pinfunction "2_2") (pintype "passive"))
    )
    (net (code "58") (name "Net-(LED6-PadA)") (class "Default")
      (node (ref "LED6") (pin "A") (pinfunction "A_A") (pintype "passive"))
      (node (ref "R55") (pin "2") (pinfunction "2_2") (pintype "passive"))
    )
    (net (code "59") (name "Net-(Q1-D)") (class "Default")
      (node (ref "Q1") (pin "3") (pinfunction "D_3") (pintype "passive"))
      (node (ref "R58") (pin "2") (pinfunction "2_2") (pintype "passive"))
    )
    (net (code "60") (name "Net-(Q1-G)") (class "Default")
      (node (ref "Q1") (pin "1") (pinfunction "G_1") (pintype "passive"))
      (node (ref "R7") (pin "1") (pinfunction "1_1") (pintype "passive"))
      (node (ref "R8") (pin "1") (pinfunction "1_1") (pintype "passive"))
    )
    (net (code "61") (name "Net-(Q2-D)") (class "Default")
      (node (ref "Q2") (pin "3") (pinfunction "D_3") (pintype "passive"))
      (node (ref "R56") (pin "2") (pinfunction "2_2") (pintype "passive"))
    )
    (net (code "62") (name "Net-(Q2-G)") (class "Default")
      (node (ref "Q2") (pin "1") (pinfunction "G_1") (pintype "passive"))
      (node (ref "R33") (pin "1") (pinfunction "1_1") (pintype "passive"))
      (node (ref "R34") (pin "1") (pinfunction "1_1") (pintype "passive"))
    )
    (net (code "63") (name "Net-(R15-Pad1)") (class "Default")
      (node (ref "R15") (pin "1") (pinfunction "1_1") (pintype "passive"))
      (node (ref "R16") (pin "2") (pinfunction "2_2") (pintype "passive"))
      (node (ref "S2") (pin "2") (pinfunction "2_2") (pintype "passive"))
    )
    (net (code "64") (name "Net-(R47-Pad1)") (class "Default")
      (node (ref "R47") (pin "1") (pinfunction "1_1") (pintype "passive"))
      (node (ref "R48") (pin "2") (pinfunction "2_2") (pintype "passive"))
      (node (ref "S1") (pin "2") (pinfunction "2_2") (pintype "passive"))
    )
    (net (code "65") (name "Net-(U1--IN)") (class "Default")
      (node (ref "C15") (pin "2") (pinfunction "2_2") (pintype "passive"))
      (node (ref "R10") (pin "2") (pinfunction "2_2") (pintype "passive"))
      (node (ref "R32") (pin "2") (pinfunction "2_2") (pintype "passive"))
      (node (ref "U1") (pin "2") (pinfunction "-IN_2") (pintype "input"))
    )
    (net (code "66") (name "Net-(U1-OUT)") (class "Default")
      (node (ref "C15") (pin "1") (pinfunction "1_1") (pintype "passive"))
      (node (ref "R25") (pin "1") (pinfunction "1_1") (pintype "passive"))
      (node (ref "R32") (pin "1") (pinfunction "1_1") (pintype "passive"))
      (node (ref "U1") (pin "6") (pinfunction "OUT_6") (pintype "output"))
      (node (ref "U3") (pin "3") (pinfunction "+IN_3") (pintype "input"))
    )
    (net (code "67") (name "Net-(U3--IN)") (class "Default")
      (node (ref "C3") (pin "2") (pinfunction "2_2") (pintype "passive"))
      (node (ref "R17") (pin "1") (pinfunction "1_1") (pintype "passive"))
      (node (ref "R18") (pin "1") (pinfunction "1_1") (pintype "passive"))
      (node (ref "U3") (pin "2") (pinfunction "-IN_2") (pintype "input"))
    )
    (net (code "68") (name "Net-(U4-+IN)") (class "Default")
      (node (ref "C5") (pin "2") (pinfunction "2_2") (pintype "passive"))
      (node (ref "R26") (pin "2") (pinfunction "2_2") (pintype "passive"))
      (node (ref "U4") (pin "3") (pinfunction "+IN_3") (pintype "input"))
    )
    (net (code "69") (name "Net-(U5-DRAIN0)") (class "Default")
      (node (ref "R40") (pin "1") (pinfunction "1_1") (pintype "passive"))
      (node (ref "U5") (pin "3") (pinfunction "DRAIN0_3") (pintype "bidirectional"))
    )
    (net (code "70") (name "Net-(U5-DRAIN1)") (class "Default")
      (node (ref "R39") (pin "1") (pinfunction "1_1") (pintype "passive"))
      (node (ref "U5") (pin "4") (pinfunction "DRAIN1_4") (pintype "bidirectional"))
    )
    (net (code "71") (name "Net-(U5-DRAIN2)") (class "Default")
      (node (ref "R38") (pin "1") (pinfunction "1_1") (pintype "passive"))
      (node (ref "U5") (pin "5") (pinfunction "DRAIN2_5") (pintype "bidirectional"))
    )
    (net (code "72") (name "Net-(U5-DRAIN3)") (class "Default")
      (node (ref "R37") (pin "1") (pinfunction "1_1") (pintype "passive"))
      (node (ref "U5") (pin "6") (pinfunction "DRAIN3_6") (pintype "bidirectional"))
    )
    (net (code "73") (name "Net-(U5-DRAIN4)") (class "Default")
      (node (ref "R44") (pin "1") (pinfunction "1_1") (pintype "passive"))
      (node (ref "U5") (pin "11") (pinfunction "DRAIN4_11") (pintype "bidirectional"))
    )
    (net (code "74") (name "Net-(U5-DRAIN5)") (class "Default")
      (node (ref "R43") (pin "1") (pinfunction "1_1") (pintype "passive"))
      (node (ref "U5") (pin "12") (pinfunction "DRAIN5_12") (pintype "bidirectional"))
    )
    (net (code "75") (name "Net-(U5-DRAIN6)") (class "Default")
      (node (ref "R42") (pin "1") (pinfunction "1_1") (pintype "passive"))
      (node (ref "U5") (pin "13") (pinfunction "DRAIN6_13") (pintype "bidirectional"))
    )
    (net (code "76") (name "Net-(U5-DRAIN7)") (class "Default")
      (node (ref "R41") (pin "1") (pinfunction "1_1") (pintype "passive"))
      (node (ref "U5") (pin "14") (pinfunction "DRAIN7_14") (pintype "bidirectional"))
    )
    (net (code "77") (name "Net-(U5-SCL)") (class "Default")
      (node (ref "R19") (pin "1") (pinfunction "1_1") (pintype "passive"))
      (node (ref "U5") (pin "15") (pinfunction "SCL_15") (pintype "bidirectional"))
    )
    (net (code "78") (name "Net-(U5-SDA)") (class "Default")
      (node (ref "R23") (pin "1") (pinfunction "1_1") (pintype "passive"))
      (node (ref "U5") (pin "2") (pinfunction "SDA_2") (pintype "bidirectional"))
    )
    (net (code "79") (name "Net-(U6-+IN)") (class "Default")
      (node (ref "R28") (pin "2") (pinfunction "2_2") (pintype "passive"))
      (node (ref "U6") (pin "3") (pinfunction "+IN_3") (pintype "input"))
    )
    (net (code "80") (name "Net-(U6--IN)") (class "Default")
      (node (ref "JP1") (pin "1") (pinfunction "1_1") (pintype "passive"))
      (node (ref "R35") (pin "2") (pinfunction "2_2") (pintype "passive"))
      (node (ref "R36") (pin "1") (pinfunction "1_1") (pintype "passive"))
      (node (ref "R37") (pin "2") (pinfunction "2_2") (pintype "passive"))
      (node (ref "R38") (pin "2") (pinfunction "2_2") (pintype "passive"))
      (node (ref "R39") (pin "2") (pinfunction "2_2") (pintype "passive"))
      (node (ref "R40") (pin "2") (pinfunction "2_2") (pintype "passive"))
      (node (ref "R41") (pin "2") (pinfunction "2_2") (pintype "passive"))
      (node (ref "R42") (pin "2") (pinfunction "2_2") (pintype "passive"))
      (node (ref "R43") (pin "2") (pinfunction "2_2") (pintype "passive"))
      (node (ref "R44") (pin "2") (pinfunction "2_2") (pintype "passive"))
      (node (ref "U6") (pin "2") (pinfunction "-IN_2") (pintype "input"))
    )
    (net (code "81") (name "RETURN") (class "Default")
      (node (ref "MACHINE1") (pin "1") (pinfunction "1_1") (pintype "passive"))
      (node (ref "MACHINE1") (pin "4") (pinfunction "4_4") (pintype "passive"))
      (node (ref "MACHINE1") (pin "5") (pinfunction "5_5") (pintype "passive"))
      (node (ref "MACHINE2") (pin "1") (pinfunction "1_1") (pintype "passive"))
      (node (ref "MACHINE2") (pin "4") (pinfunction "4_4") (pintype "passive"))
      (node (ref "MACHINE2") (pin "5") (pinfunction "5_5") (pintype "passive"))
      (node (ref "RSENSE") (pin "1") (pinfunction "1_1") (pintype "passive"))
      (node (ref "U1") (pin "3") (pinfunction "+IN_3") (pintype "input"))
    )
    (net (code "82") (name "SCL") (class "Default")
      (node (ref "IC1") (pin "12") (pinfunction "SCL_12") (pintype "input"))
      (node (ref "J1") (pin "3") (pinfunction "3_3") (pintype "passive"))
      (node (ref "R19") (pin "2") (pinfunction "2_2") (pintype "passive"))
      (node (ref "R53") (pin "1") (pinfunction "1_1") (pintype "passive"))
    )
    (net (code "83") (name "SDA") (class "Default")
      (node (ref "IC1") (pin "13") (pinfunction "SDA_13") (pintype "bidirectional"))
      (node (ref "J1") (pin "2") (pinfunction "2_2") (pintype "passive"))
      (node (ref "R23") (pin "2") (pinfunction "2_2") (pintype "passive"))
      (node (ref "R54") (pin "1") (pinfunction "1_1") (pintype "passive"))
    )
    (net (code "84") (name "VIN+") (class "Default")
      (node (ref "C12") (pin "2") (pinfunction "2_2") (pintype "passive"))
      (node (ref "C9") (pin "2") (pinfunction "2_2") (pintype "passive"))
      (node (ref "R52") (pin "1") (pinfunction "1_1") (pintype "passive"))
      (node (ref "RCA") (pin "2") (pinfunction "2_2") (pintype "passive"))
      (node (ref "RCA") (pin "3") (pinfunction "3_3") (pintype "passive"))
      (node (ref "U2") (pin "1") (pinfunction "VIN_1") (pintype "input"))
    )
    (net (code "85") (name "unconnected-(IC1-GPA3-Pad24)") (class "Default")
      (node (ref "IC1") (pin "24") (pinfunction "GPA3_24") (pintype "bidirectional"))
    )
    (net (code "86") (name "unconnected-(IC1-GPA4-Pad25)") (class "Default")
      (node (ref "IC1") (pin "25") (pinfunction "GPA4_25") (pintype "bidirectional"))
    )
    (net (code "87") (name "unconnected-(IC1-GPA6-Pad27)") (class "Default")
      (node (ref "IC1") (pin "27") (pinfunction "GPA6_27") (pintype "bidirectional"))
    )
    (net (code "88") (name "unconnected-(IC1-GPA7-Pad28)") (class "Default")
      (node (ref "IC1") (pin "28") (pinfunction "GPA7_28") (pintype "bidirectional"))
    )
    (net (code "89") (name "unconnected-(IC1-GPB0-Pad1)") (class "Default")
      (node (ref "IC1") (pin "1") (pinfunction "GPB0_1") (pintype "bidirectional"))
    )
    (net (code "90") (name "unconnected-(IC1-GPB1-Pad2)") (class "Default")
      (node (ref "IC1") (pin "2") (pinfunction "GPB1_2") (pintype "bidirectional"))
    )
    (net (code "91") (name "unconnected-(IC1-GPB6-Pad7)") (class "Default")
      (node (ref "IC1") (pin "7") (pinfunction "GPB6_7") (pintype "bidirectional"))
    )
    (net (code "92") (name "unconnected-(IC1-GPB7-Pad8)") (class "Default")
      (node (ref "IC1") (pin "8") (pinfunction "GPB7_8") (pintype "bidirectional"))
    )
    (net (code "93") (name "unconnected-(IC1-INTA-Pad20)") (class "Default")
      (node (ref "IC1") (pin "20") (pinfunction "INTA_20") (pintype "output"))
    )
    (net (code "94") (name "unconnected-(IC1-INTB-Pad19)") (class "Default")
      (node (ref "IC1") (pin "19") (pinfunction "INTB_19") (pintype "output"))
    )
    (net (code "95") (name "unconnected-(J1-Pad5)") (class "Default")
      (node (ref "J1") (pin "5") (pinfunction "5_5") (pintype "passive"))
    )
    (net (code "96") (name "unconnected-(MACHINE1-Pad2)") (class "Default")
      (node (ref "MACHINE1") (pin "2") (pinfunction "2_2") (pintype "passive"))
    )
    (net (code "97") (name "unconnected-(MACHINE1-Pad3)") (class "Default")
      (node (ref "MACHINE1") (pin "3") (pinfunction "3_3") (pintype "passive"))
    )
    (net (code "98") (name "unconnected-(MACHINE2-Pad2)") (class "Default")
      (node (ref "MACHINE2") (pin "2") (pinfunction "2_2") (pintype "passive"))
    )
    (net (code "99") (name "unconnected-(MACHINE2-Pad3)") (class "Default")
      (node (ref "MACHINE2") (pin "3") (pinfunction "3_3") (pintype "passive"))
    )
    (net (code "100") (name "unconnected-(S1-Pad1)") (class "Default")
      (node (ref "S1") (pin "1") (pinfunction "1_1") (pintype "passive"))
    )
    (net (code "101") (name "unconnected-(S1-Pad3)") (class "Default")
      (node (ref "S1") (pin "3") (pinfunction "3_3") (pintype "passive"))
    )
    (net (code "102") (name "unconnected-(S2-Pad1)") (class "Default")
      (node (ref "S2") (pin "1") (pinfunction "1_1") (pintype "passive"))
    )
    (net (code "103") (name "unconnected-(S2-Pad3)") (class "Default")
      (node (ref "S2") (pin "3") (pinfunction "3_3") (pintype "passive"))
    )
    (net (code "104") (name "unconnected-(U7-Pad3V3_EN)") (class "Default")
      (node (ref "U7") (pin "3V3_EN") (pinfunction "3V3_EN_3V3_EN") (pintype "bidirectional"))
    )
    (net (code "105") (name "unconnected-(U7-PadADC_VREF)") (class "Default")
      (node (ref "U7") (pin "ADC_VREF") (pinfunction "ADC_VREF_ADC_VREF") (pintype "bidirectional"))
    )
    (net (code "106") (name "unconnected-(U7-PadGP0)") (class "Default")
      (node (ref "U7") (pin "GP0") (pinfunction "GP0_GP0") (pintype "bidirectional"))
    )
    (net (code "107") (name "unconnected-(U7-PadGP1)") (class "Default")
      (node (ref "U7") (pin "GP1") (pinfunction "GP1_GP1") (pintype "bidirectional"))
    )
    (net (code "108") (name "unconnected-(U7-PadGP6)") (class "Default")
      (node (ref "U7") (pin "GP6") (pinfunction "GP6_GP6") (pintype "bidirectional"))
    )
    (net (code "109") (name "unconnected-(U7-PadGP7)") (class "Default")
      (node (ref "U7") (pin "GP7") (pinfunction "GP7_GP7") (pintype "bidirectional"))
    )
    (net (code "110") (name "unconnected-(U7-PadGP8)") (class "Default")
      (node (ref "U7") (pin "GP8") (pinfunction "GP8_GP8") (pintype "bidirectional"))
    )
    (net (code "111") (name "unconnected-(U7-PadGP9)") (class "Default")
      (node (ref "U7") (pin "GP9") (pinfunction "GP9_GP9") (pintype "bidirectional"))
    )
    (net (code "112") (name "unconnected-(U7-PadGP12)") (class "Default")
      (node (ref "U7") (pin "GP12") (pinfunction "GP12_GP12") (pintype "bidirectional"))
    )
    (net (code "113") (name "unconnected-(U7-PadGP13)") (class "Default")
      (node (ref "U7") (pin "GP13") (pinfunction "GP13_GP13") (pintype "bidirectional"))
    )
    (net (code "114") (name "unconnected-(U7-PadGP22)") (class "Default")
      (node (ref "U7") (pin "GP22") (pinfunction "GP22_GP22") (pintype "bidirectional"))
    )
    (net (code "115") (name "unconnected-(U7-PadRUN)") (class "Default")
      (node (ref "U7") (pin "RUN") (pinfunction "RUN_RUN") (pintype "bidirectional"))
    )
    (net (code "116") (name "unconnected-(U7-PadVBUS)") (class "Default")
      (node (ref "U7") (pin "VBUS") (pinfunction "VBUS_VBUS") (pintype "bidirectional"))
    )
    (net (code "117") (name "unconnected-(U7-PadVSYS)") (class "Default")
      (node (ref "U7") (pin "VSYS") (pinfunction "VSYS_VSYS") (pintype "bidirectional"))
    )
  )
)
